# Ring_5_A.net
KiCad netlist of a schematic drawn in Altium Designer
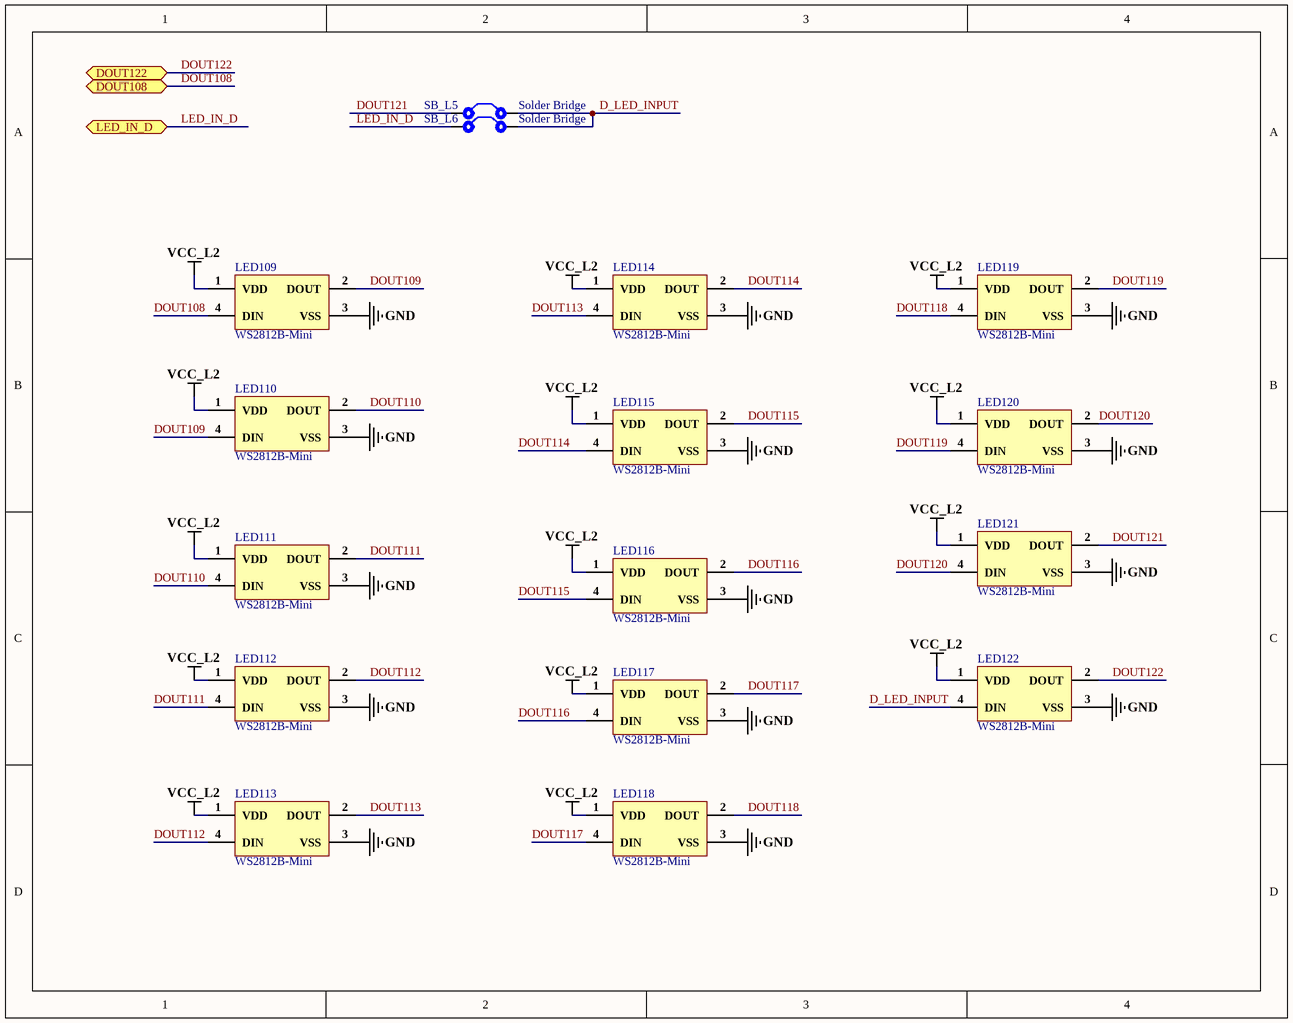
[diagram p0: Ring 5_A.SchDoc]

(export (version "E")
  (design (tool "Eeschema 10.0.6"))
  (components
    (comp (ref "LED109")
      (value "WS2812B-Mini")
      (footprint "WS2812B-Mini")
      (description "SMD,3.5x3.5mm Light Emitting Diodes (LED) RoHS")
      (fields (field (name "MANUFACTURER") "Worldsemi"))
      (libsource (lib "TT_IntLib") (part "WS2812B-Mini"))
    )
    (comp (ref "LED110")
      (value "WS2812B-Mini")
      (footprint "WS2812B-Mini")
      (description "SMD,3.5x3.5mm Light Emitting Diodes (LED) RoHS")
      (fields (field (name "MANUFACTURER") "Worldsemi"))
      (libsource (lib "TT_IntLib") (part "WS2812B-Mini"))
    )
    (comp (ref "LED111")
      (value "WS2812B-Mini")
      (footprint "WS2812B-Mini")
      (description "SMD,3.5x3.5mm Light Emitting Diodes (LED) RoHS")
      (fields (field (name "MANUFACTURER") "Worldsemi"))
      (libsource (lib "TT_IntLib") (part "WS2812B-Mini"))
    )
    (comp (ref "LED112")
      (value "WS2812B-Mini")
      (footprint "WS2812B-Mini")
      (description "SMD,3.5x3.5mm Light Emitting Diodes (LED) RoHS")
      (fields (field (name "MANUFACTURER") "Worldsemi"))
      (libsource (lib "TT_IntLib") (part "WS2812B-Mini"))
    )
    (comp (ref "LED113")
      (value "WS2812B-Mini")
      (footprint "WS2812B-Mini")
      (description "SMD,3.5x3.5mm Light Emitting Diodes (LED) RoHS")
      (fields (field (name "MANUFACTURER") "Worldsemi"))
      (libsource (lib "TT_IntLib") (part "WS2812B-Mini"))
    )
    (comp (ref "LED114")
      (value "WS2812B-Mini")
      (footprint "WS2812B-Mini")
      (description "SMD,3.5x3.5mm Light Emitting Diodes (LED) RoHS")
      (fields (field (name "MANUFACTURER") "Worldsemi"))
      (libsource (lib "TT_IntLib") (part "WS2812B-Mini"))
    )
    (comp (ref "LED115")
      (value "WS2812B-Mini")
      (footprint "WS2812B-Mini")
      (description "SMD,3.5x3.5mm Light Emitting Diodes (LED) RoHS")
      (fields (field (name "MANUFACTURER") "Worldsemi"))
      (libsource (lib "TT_IntLib") (part "WS2812B-Mini"))
    )
    (comp (ref "LED116")
      (value "WS2812B-Mini")
      (footprint "WS2812B-Mini")
      (description "SMD,3.5x3.5mm Light Emitting Diodes (LED) RoHS")
      (fields (field (name "MANUFACTURER") "Worldsemi"))
      (libsource (lib "TT_IntLib") (part "WS2812B-Mini"))
    )
    (comp (ref "LED117")
      (value "WS2812B-Mini")
      (footprint "WS2812B-Mini")
      (description "SMD,3.5x3.5mm Light Emitting Diodes (LED) RoHS")
      (fields (field (name "MANUFACTURER") "Worldsemi"))
      (libsource (lib "TT_IntLib") (part "WS2812B-Mini"))
    )
    (comp (ref "LED118")
      (value "WS2812B-Mini")
      (footprint "WS2812B-Mini")
      (description "SMD,3.5x3.5mm Light Emitting Diodes (LED) RoHS")
      (fields (field (name "MANUFACTURER") "Worldsemi"))
      (libsource (lib "TT_IntLib") (part "WS2812B-Mini"))
    )
    (comp (ref "LED119")
      (value "WS2812B-Mini")
      (footprint "WS2812B-Mini")
      (description "SMD,3.5x3.5mm Light Emitting Diodes (LED) RoHS")
      (fields (field (name "MANUFACTURER") "Worldsemi"))
      (libsource (lib "TT_IntLib") (part "WS2812B-Mini"))
    )
    (comp (ref "LED120")
      (value "WS2812B-Mini")
      (footprint "WS2812B-Mini")
      (description "SMD,3.5x3.5mm Light Emitting Diodes (LED) RoHS")
      (fields (field (name "MANUFACTURER") "Worldsemi"))
      (libsource (lib "TT_IntLib") (part "WS2812B-Mini"))
    )
    (comp (ref "LED121")
      (value "WS2812B-Mini")
      (footprint "WS2812B-Mini")
      (description "SMD,3.5x3.5mm Light Emitting Diodes (LED) RoHS")
      (fields (field (name "MANUFACTURER") "Worldsemi"))
      (libsource (lib "TT_IntLib") (part "WS2812B-Mini"))
    )
    (comp (ref "LED122")
      (value "WS2812B-Mini")
      (footprint "WS2812B-Mini")
      (description "SMD,3.5x3.5mm Light Emitting Diodes (LED) RoHS")
      (fields (field (name "MANUFACTURER") "Worldsemi"))
      (libsource (lib "TT_IntLib") (part "WS2812B-Mini"))
    )
    (comp (ref "SB_L5")
      (value "Solder Bridge")
      (footprint "Solder Bridge")
      (description "Solder Bridge ON")
      (libsource (lib "TT_IntLib") (part "Solder Bridge"))
    )
    (comp (ref "SB_L6")
      (value "Solder Bridge")
      (footprint "Solder Bridge")
      (description "Solder Bridge ON")
      (libsource (lib "TT_IntLib") (part "Solder Bridge"))
    )
  )
  (nets
    (net (code "1") (name "/DOUT108") (class "Default")
      (node (ref "LED109") (pin "4") (pinfunction "DIN_4") (pintype "passive"))
    )
    (net (code "2") (name "/DOUT109") (class "Default")
      (node (ref "LED109") (pin "2") (pinfunction "DOUT_2") (pintype "passive"))
      (node (ref "LED110") (pin "4") (pinfunction "DIN_4") (pintype "passive"))
    )
    (net (code "3") (name "/DOUT110") (class "Default")
      (node (ref "LED110") (pin "2") (pinfunction "DOUT_2") (pintype "passive"))
      (node (ref "LED111") (pin "4") (pinfunction "DIN_4") (pintype "passive"))
    )
    (net (code "4") (name "/DOUT111") (class "Default")
      (node (ref "LED111") (pin "2") (pinfunction "DOUT_2") (pintype "passive"))
      (node (ref "LED112") (pin "4") (pinfunction "DIN_4") (pintype "passive"))
    )
    (net (code "5") (name "/DOUT112") (class "Default")
      (node (ref "LED112") (pin "2") (pinfunction "DOUT_2") (pintype "passive"))
      (node (ref "LED113") (pin "4") (pinfunction "DIN_4") (pintype "passive"))
    )
    (net (code "6") (name "/DOUT113") (class "Default")
      (node (ref "LED113") (pin "2") (pinfunction "DOUT_2") (pintype "passive"))
      (node (ref "LED114") (pin "4") (pinfunction "DIN_4") (pintype "passive"))
    )
    (net (code "7") (name "/DOUT114") (class "Default")
      (node (ref "LED114") (pin "2") (pinfunction "DOUT_2") (pintype "passive"))
      (node (ref "LED115") (pin "4") (pinfunction "DIN_4") (pintype "passive"))
    )
    (net (code "8") (name "/DOUT115") (class "Default")
      (node (ref "LED115") (pin "2") (pinfunction "DOUT_2") (pintype "passive"))
      (node (ref "LED116") (pin "4") (pinfunction "DIN_4") (pintype "passive"))
    )
    (net (code "9") (name "/DOUT116") (class "Default")
      (node (ref "LED116") (pin "2") (pinfunction "DOUT_2") (pintype "passive"))
      (node (ref "LED117") (pin "4") (pinfunction "DIN_4") (pintype "passive"))
    )
    (net (code "10") (name "/DOUT117") (class "Default")
      (node (ref "LED117") (pin "2") (pinfunction "DOUT_2") (pintype "passive"))
      (node (ref "LED118") (pin "4") (pinfunction "DIN_4") (pintype "passive"))
    )
    (net (code "11") (name "/DOUT118") (class "Default")
      (node (ref "LED118") (pin "2") (pinfunction "DOUT_2") (pintype "passive"))
      (node (ref "LED119") (pin "4") (pinfunction "DIN_4") (pintype "passive"))
    )
    (net (code "12") (name "/DOUT119") (class "Default")
      (node (ref "LED119") (pin "2") (pinfunction "DOUT_2") (pintype "passive"))
      (node (ref "LED120") (pin "4") (pinfunction "DIN_4") (pintype "passive"))
    )
    (net (code "13") (name "/DOUT120") (class "Default")
      (node (ref "LED120") (pin "2") (pinfunction "DOUT_2") (pintype "passive"))
      (node (ref "LED121") (pin "4") (pinfunction "DIN_4") (pintype "passive"))
    )
    (net (code "14") (name "/DOUT121") (class "Default")
      (node (ref "LED121") (pin "2") (pinfunction "DOUT_2") (pintype "passive"))
      (node (ref "SB_L5") (pin "1") (pinfunction "1_1") (pintype "passive"))
    )
    (net (code "15") (name "/DOUT122") (class "Default")
      (node (ref "LED122") (pin "2") (pinfunction "DOUT_2") (pintype "passive"))
    )
    (net (code "16") (name "/D_LED_INPUT") (class "Default")
      (node (ref "LED122") (pin "4") (pinfunction "DIN_4") (pintype "passive"))
      (node (ref "SB_L5") (pin "2") (pinfunction "2_2") (pintype "passive"))
      (node (ref "SB_L6") (pin "2") (pinfunction "2_2") (pintype "passive"))
    )
    (net (code "17") (name "/LED_IN_D") (class "Default")
      (node (ref "SB_L6") (pin "1") (pinfunction "1_1") (pintype "passive"))
    )
    (net (code "18") (name "GND") (class "Default")
      (node (ref "LED109") (pin "3") (pinfunction "VSS_3") (pintype "passive"))
      (node (ref "LED110") (pin "3") (pinfunction "VSS_3") (pintype "passive"))
      (node (ref "LED111") (pin "3") (pinfunction "VSS_3") (pintype "passive"))
      (node (ref "LED112") (pin "3") (pinfunction "VSS_3") (pintype "passive"))
      (node (ref "LED113") (pin "3") (pinfunction "VSS_3") (pintype "passive"))
      (node (ref "LED114") (pin "3") (pinfunction "VSS_3") (pintype "passive"))
      (node (ref "LED115") (pin "3") (pinfunction "VSS_3") (pintype "passive"))
      (node (ref "LED116") (pin "3") (pinfunction "VSS_3") (pintype "passive"))
      (node (ref "LED117") (pin "3") (pinfunction "VSS_3") (pintype "passive"))
      (node (ref "LED118") (pin "3") (pinfunction "VSS_3") (pintype "passive"))
      (node (ref "LED119") (pin "3") (pinfunction "VSS_3") (pintype "passive"))
      (node (ref "LED120") (pin "3") (pinfunction "VSS_3") (pintype "passive"))
      (node (ref "LED121") (pin "3") (pinfunction "VSS_3") (pintype "passive"))
      (node (ref "LED122") (pin "3") (pinfunction "VSS_3") (pintype "passive"))
    )
    (net (code "19") (name "VCC_L2") (class "Default")
      (node (ref "LED109") (pin "1") (pinfunction "VDD_1") (pintype "passive"))
      (node (ref "LED110") (pin "1") (pinfunction "VDD_1") (pintype "passive"))
      (node (ref "LED111") (pin "1") (pinfunction "VDD_1") (pintype "passive"))
      (node (ref "LED112") (pin "1") (pinfunction "VDD_1") (pintype "passive"))
      (node (ref "LED113") (pin "1") (pinfunction "VDD_1") (pintype "passive"))
      (node (ref "LED114") (pin "1") (pinfunction "VDD_1") (pintype "passive"))
      (node (ref "LED115") (pin "1") (pinfunction "VDD_1") (pintype "passive"))
      (node (ref "LED116") (pin "1") (pinfunction "VDD_1") (pintype "passive"))
      (node (ref "LED117") (pin "1") (pinfunction "VDD_1") (pintype "passive"))
      (node (ref "LED118") (pin "1") (pinfunction "VDD_1") (pintype "passive"))
      (node (ref "LED119") (pin "1") (pinfunction "VDD_1") (pintype "passive"))
      (node (ref "LED120") (pin "1") (pinfunction "VDD_1") (pintype "passive"))
      (node (ref "LED121") (pin "1") (pinfunction "VDD_1") (pintype "passive"))
      (node (ref "LED122") (pin "1") (pinfunction "VDD_1") (pintype "passive"))
    )
  )
)
